# Dual-Port_Logging_Shield.net
KiCad netlist of a schematic drawn in EAGLE
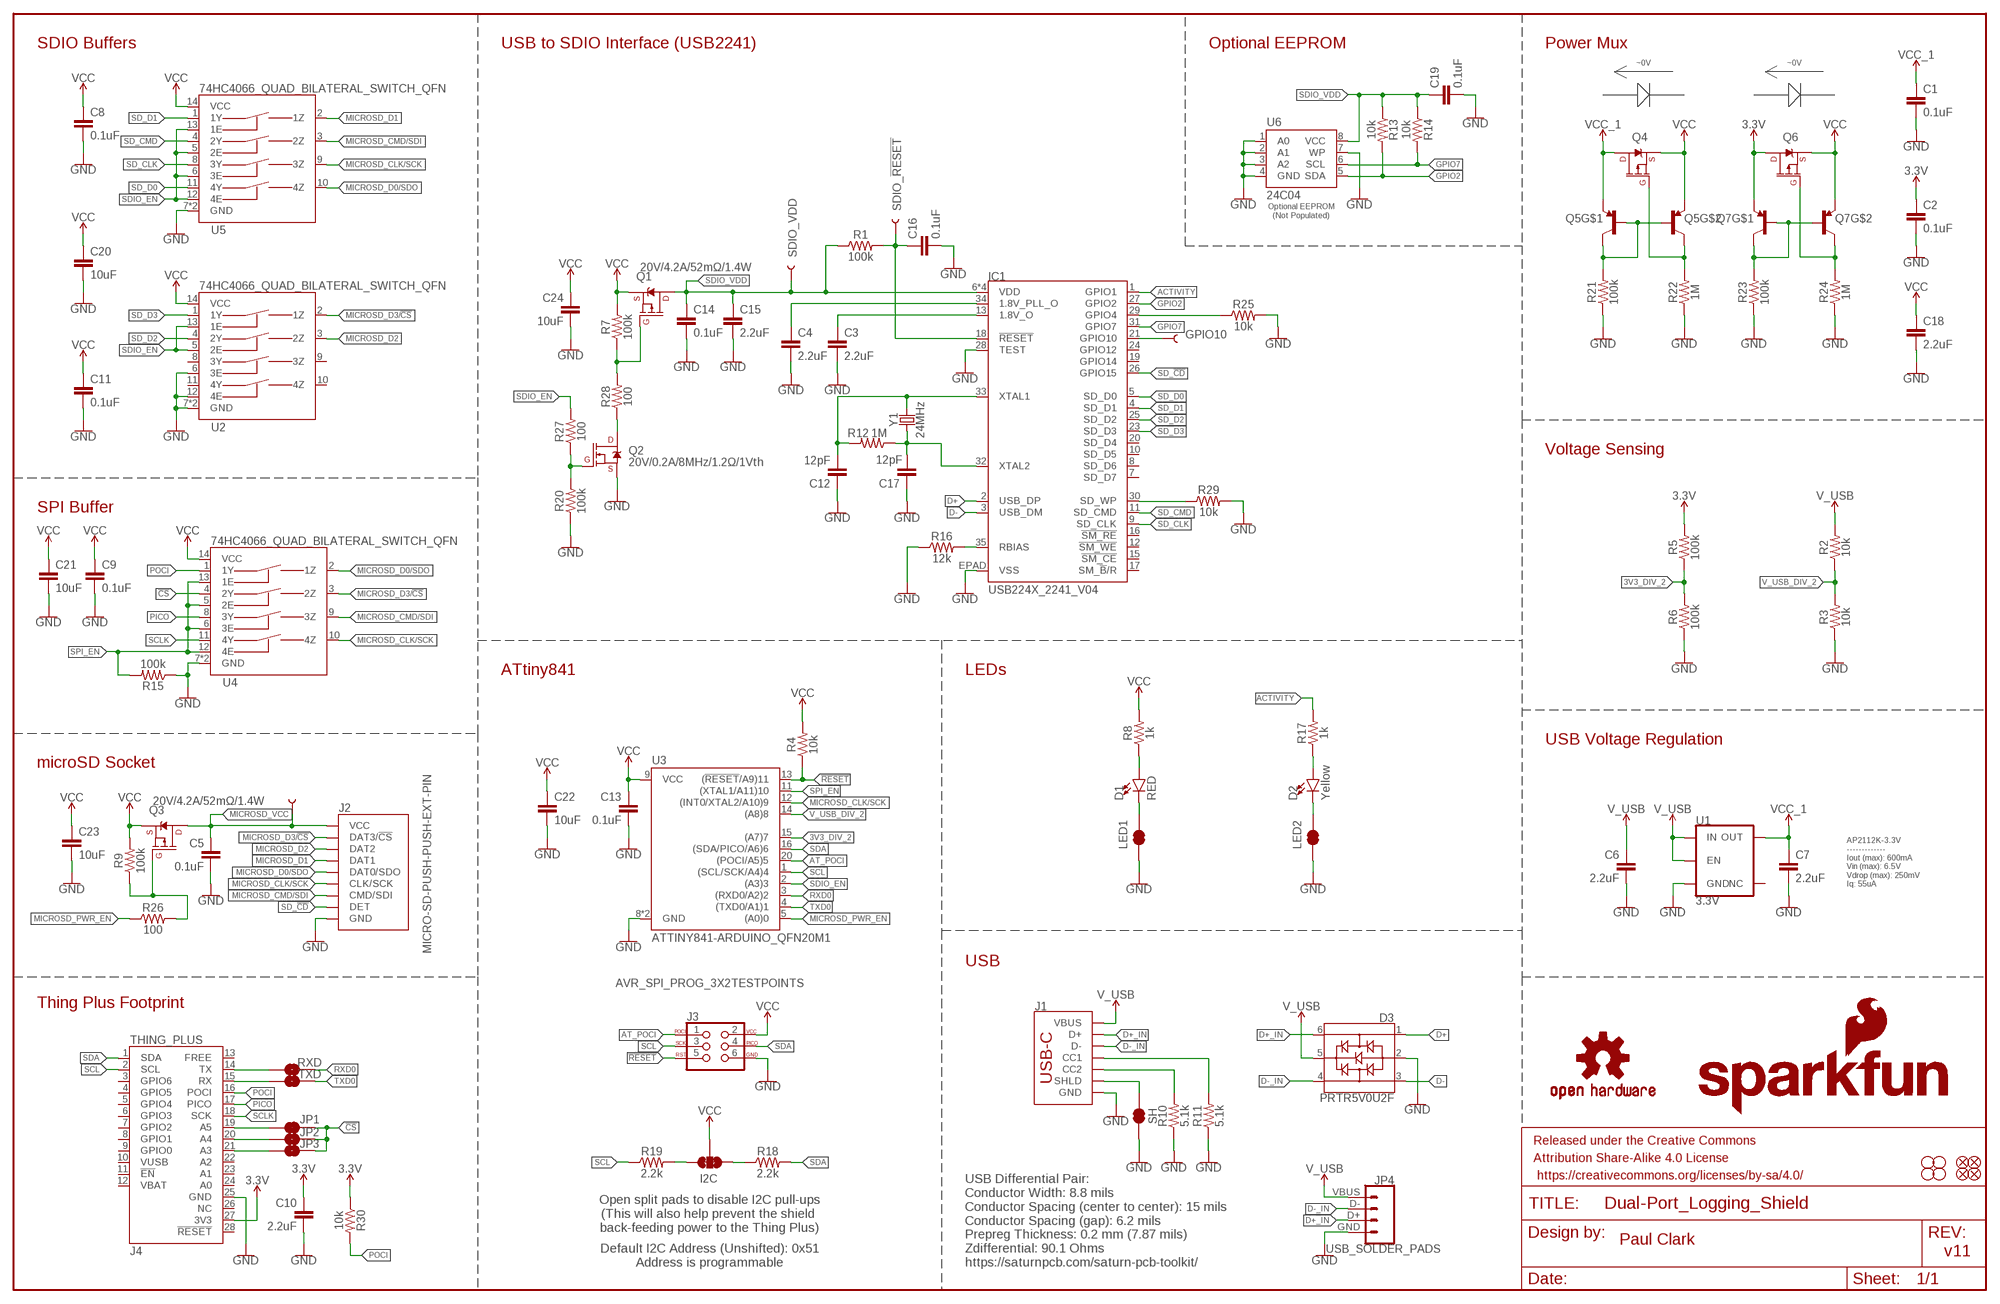
[diagram p0: schematic, sheet 1]

(export (version "E")
  (design (tool "Eeschema 10.0.6"))
  (components
    (comp (ref "C1")
      (value "0.1uF")
      (footprint "eagle-import:0402-TIGHT")
      (libsource (lib "eagle-import") (part "0.1UF-0402T-6.3V-10%-X7R"))
    )
    (comp (ref "C2")
      (value "0.1uF")
      (footprint "eagle-import:0402-TIGHT")
      (libsource (lib "eagle-import") (part "0.1UF-0402T-6.3V-10%-X7R"))
    )
    (comp (ref "C3")
      (value "2.2uF")
      (footprint "eagle-import:0402-TIGHT")
      (libsource (lib "eagle-import") (part "2.2UF-0402_TIGHT-10V-10%-X5R"))
    )
    (comp (ref "C4")
      (value "2.2uF")
      (footprint "eagle-import:0402-TIGHT")
      (libsource (lib "eagle-import") (part "2.2UF-0402_TIGHT-10V-10%-X5R"))
    )
    (comp (ref "C5")
      (value "0.1uF")
      (footprint "eagle-import:0402-TIGHT")
      (libsource (lib "eagle-import") (part "0.1UF-0402T-6.3V-10%-X7R"))
    )
    (comp (ref "C6")
      (value "2.2uF")
      (footprint "eagle-import:0402-TIGHT")
      (libsource (lib "eagle-import") (part "2.2UF-0402_TIGHT-10V-10%-X5R"))
    )
    (comp (ref "C7")
      (value "2.2uF")
      (footprint "eagle-import:0402-TIGHT")
      (libsource (lib "eagle-import") (part "2.2UF-0402_TIGHT-10V-10%-X5R"))
    )
    (comp (ref "C8")
      (value "0.1uF")
      (footprint "eagle-import:0402-TIGHT")
      (libsource (lib "eagle-import") (part "0.1UF-0402T-6.3V-10%-X7R"))
    )
    (comp (ref "C9")
      (value "0.1uF")
      (footprint "eagle-import:0402-TIGHT")
      (libsource (lib "eagle-import") (part "0.1UF-0402T-6.3V-10%-X7R"))
    )
    (comp (ref "C10")
      (value "2.2uF")
      (footprint "eagle-import:0402-TIGHT")
      (libsource (lib "eagle-import") (part "2.2UF-0402_TIGHT-10V-10%-X5R"))
    )
    (comp (ref "C11")
      (value "0.1uF")
      (footprint "eagle-import:0402-TIGHT")
      (libsource (lib "eagle-import") (part "0.1UF-0402T-6.3V-10%-X7R"))
    )
    (comp (ref "C12")
      (value "12pF")
      (footprint "eagle-import:0402-TIGHT")
      (libsource (lib "eagle-import") (part "12PF-0402T-50V-5%"))
    )
    (comp (ref "C13")
      (value "0.1uF")
      (footprint "eagle-import:0402-TIGHT")
      (libsource (lib "eagle-import") (part "0.1UF-0402T-6.3V-10%-X7R"))
    )
    (comp (ref "C14")
      (value "0.1uF")
      (footprint "eagle-import:0402-TIGHT")
      (libsource (lib "eagle-import") (part "0.1UF-0402T-6.3V-10%-X7R"))
    )
    (comp (ref "C15")
      (value "2.2uF")
      (footprint "eagle-import:0402-TIGHT")
      (libsource (lib "eagle-import") (part "2.2UF-0402_TIGHT-10V-10%-X5R"))
    )
    (comp (ref "C16")
      (value "0.1uF")
      (footprint "eagle-import:0402-TIGHT")
      (libsource (lib "eagle-import") (part "0.1UF-0402T-6.3V-10%-X7R"))
    )
    (comp (ref "C17")
      (value "12pF")
      (footprint "eagle-import:0402-TIGHT")
      (libsource (lib "eagle-import") (part "12PF-0402T-50V-5%"))
    )
    (comp (ref "C18")
      (value "2.2uF")
      (footprint "eagle-import:0402-TIGHT")
      (libsource (lib "eagle-import") (part "2.2UF-0402_TIGHT-10V-10%-X5R"))
    )
    (comp (ref "C19")
      (value "0.1uF")
      (footprint "eagle-import:0402-TIGHT")
      (libsource (lib "eagle-import") (part "0.1UF-0402T-6.3V-10%-X7R"))
    )
    (comp (ref "C20")
      (value "10uF")
      (footprint "eagle-import:0402-TIGHT")
      (libsource (lib "eagle-import") (part "10UF-0402T-6.3V-20%"))
    )
    (comp (ref "C21")
      (value "10uF")
      (footprint "eagle-import:0402-TIGHT")
      (libsource (lib "eagle-import") (part "10UF-0402T-6.3V-20%"))
    )
    (comp (ref "C22")
      (value "10uF")
      (footprint "eagle-import:0402-TIGHT")
      (libsource (lib "eagle-import") (part "10UF-0402T-6.3V-20%"))
    )
    (comp (ref "C23")
      (value "10uF")
      (footprint "eagle-import:0402-TIGHT")
      (libsource (lib "eagle-import") (part "10UF-0402T-6.3V-20%"))
    )
    (comp (ref "C24")
      (value "10uF")
      (footprint "eagle-import:0402-TIGHT")
      (libsource (lib "eagle-import") (part "10UF-0402T-6.3V-20%"))
    )
    (comp (ref "D1")
      (value "RED")
      (footprint "eagle-import:LED-0603")
      (libsource (lib "eagle-import") (part "LED-RED0603"))
    )
    (comp (ref "D2")
      (value "Yellow")
      (footprint "eagle-import:LED-0603")
      (libsource (lib "eagle-import") (part "LED-YELLOW0603"))
    )
    (comp (ref "D3")
      (value "PRTR5V0U2F")
      (footprint "eagle-import:SOT886")
      (libsource (lib "eagle-import") (part "PRTR5V0U2F"))
    )
    (comp (ref "FD1")
      (value "FIDUCIALUFIDUCIAL")
      (footprint "eagle-import:FIDUCIAL-MICRO")
      (libsource (lib "eagle-import") (part "FIDUCIALUFIDUCIAL"))
    )
    (comp (ref "FD2")
      (value "FIDUCIALUFIDUCIAL")
      (footprint "eagle-import:FIDUCIAL-MICRO")
      (libsource (lib "eagle-import") (part "FIDUCIALUFIDUCIAL"))
    )
    (comp (ref "FD3")
      (value "FIDUCIALUFIDUCIAL")
      (footprint "eagle-import:FIDUCIAL-MICRO")
      (libsource (lib "eagle-import") (part "FIDUCIALUFIDUCIAL"))
    )
    (comp (ref "FD4")
      (value "FIDUCIALUFIDUCIAL")
      (footprint "eagle-import:FIDUCIAL-MICRO")
      (libsource (lib "eagle-import") (part "FIDUCIALUFIDUCIAL"))
    )
    (comp (ref "FRAME1")
      (value "FRAME-LEDGER")
      (footprint "eagle-import:CREATIVE_COMMONS")
      (libsource (lib "eagle-import") (part "FRAME-LEDGER"))
    )
    (comp (ref "GPIO10")
      (value "TEST-POINT3")
      (footprint "eagle-import:PAD.03X.03")
      (libsource (lib "eagle-import") (part "TEST-POINT3"))
    )
    (comp (ref "H1")
      (value "STAND-OFF")
      (footprint "eagle-import:STAND-OFF")
      (libsource (lib "eagle-import") (part "STAND-OFF"))
    )
    (comp (ref "H2")
      (value "STAND-OFF")
      (footprint "eagle-import:STAND-OFF")
      (libsource (lib "eagle-import") (part "STAND-OFF"))
    )
    (comp (ref "H3")
      (value "STAND-OFF")
      (footprint "eagle-import:STAND-OFF")
      (libsource (lib "eagle-import") (part "STAND-OFF"))
    )
    (comp (ref "H4")
      (value "STAND-OFF")
      (footprint "eagle-import:STAND-OFF")
      (libsource (lib "eagle-import") (part "STAND-OFF"))
    )
    (comp (ref "I2C")
      (value "JUMPER-SMT_3_2-NC_TRACE_SILK")
      (footprint "eagle-import:SMT-JUMPER_3_2-NC_TRACE_SILK")
      (libsource (lib "eagle-import") (part "JUMPER-SMT_3_2-NC_TRACE_SILK"))
    )
    (comp (ref "IC1")
      (value "USB224X_2241_V04")
      (footprint "eagle-import:36-QFN")
      (libsource (lib "eagle-import") (part "USB224X_2241_V04"))
    )
    (comp (ref "J1")
      (value "USB_C_4-LAYER_PADS")
      (footprint "eagle-import:USB-C-16P_4LAYER-PADS")
      (libsource (lib "eagle-import") (part "USB_C_4-LAYER_PADS"))
    )
    (comp (ref "J2")
      (value "MICRO-SD-PUSH-PUSH-EXT-PIN")
      (footprint "eagle-import:MICROSD-EXTERNALPIN")
      (libsource (lib "eagle-import") (part "MICRO-SD-PUSH-PUSH-EXT-PIN"))
    )
    (comp (ref "J3")
      (value "AVR_SPI_PROG_3X2TESTPOINTS")
      (footprint "eagle-import:2X3_TEST_POINTS")
      (libsource (lib "eagle-import") (part "AVR_SPI_PROG_3X2TESTPOINTS"))
    )
    (comp (ref "J4")
      (value "THING_PLUS")
      (footprint "eagle-import:THING_PLUS")
      (libsource (lib "eagle-import") (part "THING_PLUS"))
    )
    (comp (ref "JP1")
      (value "JUMPER-SMT_2_NC_TRACE_SILK")
      (footprint "eagle-import:SMT-JUMPER_2_NC_TRACE_SILK")
      (libsource (lib "eagle-import") (part "JUMPER-SMT_2_NC_TRACE_SILK"))
    )
    (comp (ref "JP2")
      (value "JUMPER-SMT_2_NO_SILK")
      (footprint "eagle-import:SMT-JUMPER_2_NO_SILK")
      (libsource (lib "eagle-import") (part "JUMPER-SMT_2_NO_SILK"))
    )
    (comp (ref "JP3")
      (value "JUMPER-SMT_2_NO_SILK")
      (footprint "eagle-import:SMT-JUMPER_2_NO_SILK")
      (libsource (lib "eagle-import") (part "JUMPER-SMT_2_NO_SILK"))
    )
    (comp (ref "JP4")
      (value "USB_SOLDER_PADS")
      (footprint "eagle-import:USB-SOLDER-PADS")
      (libsource (lib "eagle-import") (part "USB_SOLDER_PADS"))
    )
    (comp (ref "LED1")
      (value "JUMPER-SMT_2_NC_TRACE_SILK")
      (footprint "eagle-import:SMT-JUMPER_2_NC_TRACE_SILK")
      (libsource (lib "eagle-import") (part "JUMPER-SMT_2_NC_TRACE_SILK"))
    )
    (comp (ref "LED2")
      (value "JUMPER-SMT_2_NC_TRACE_SILK")
      (footprint "eagle-import:SMT-JUMPER_2_NC_TRACE_SILK")
      (libsource (lib "eagle-import") (part "JUMPER-SMT_2_NC_TRACE_SILK"))
    )
    (comp (ref "LOGO2")
      (value "OSHW-LOGOMINI")
      (footprint "eagle-import:OSHW-LOGO-MINI")
      (libsource (lib "eagle-import") (part "OSHW-LOGOMINI"))
    )
    (comp (ref "LOGO3")
      (value "OSHW-LOGOMINI")
      (footprint "eagle-import:OSHW-LOGO-MINI")
      (libsource (lib "eagle-import") (part "OSHW-LOGOMINI"))
    )
    (comp (ref "LOGO4")
      (value "SFE_LOGO_FLAME.2_INCH")
      (footprint "eagle-import:SFE_LOGO_FLAME_.2")
      (libsource (lib "eagle-import") (part "SFE_LOGO_FLAME.2_INCH"))
    )
    (comp (ref "LOGO5")
      (value "SFE_LOGO_NAME_FLAME.1_INCH")
      (footprint "eagle-import:SFE_LOGO_NAME_FLAME_.1")
      (libsource (lib "eagle-import") (part "SFE_LOGO_NAME_FLAME.1_INCH"))
    )
    (comp (ref "MICROSD_VCC")
      (value "TEST-POINT3")
      (footprint "eagle-import:PAD.03X.03")
      (libsource (lib "eagle-import") (part "TEST-POINT3"))
    )
    (comp (ref "Q1")
      (value "20V/4.2A/52mΩ/1.4W")
      (footprint "eagle-import:SOT23-3")
      (libsource (lib "eagle-import") (part "MOSFET_PCH-DMG2305UX-7"))
    )
    (comp (ref "Q2")
      (value "20V/0.2A/8MHz/1.2Ω/1Vth")
      (footprint "eagle-import:SOT-416FL")
      (libsource (lib "eagle-import") (part "MOSFET-NCH-RE1C002UNTCL"))
    )
    (comp (ref "Q3")
      (value "20V/4.2A/52mΩ/1.4W")
      (footprint "eagle-import:SOT23-3")
      (libsource (lib "eagle-import") (part "MOSFET_PCH-DMG2305UX-7"))
    )
    (comp (ref "Q4")
      (value "20V/4.2A/52mΩ/1.4W")
      (footprint "eagle-import:SOT23-3")
      (libsource (lib "eagle-import") (part "MOSFET_PCH-DMG2305UX-7"))
    )
    (comp (ref "Q5")
      (value "TRANS_PNP_DUALSOT-363")
      (footprint "eagle-import:SOT363_PHILIPS")
      (libsource (lib "eagle-import") (part "TRANS_PNP_DUALSOT-363"))
    )
    (comp (ref "Q6")
      (value "20V/4.2A/52mΩ/1.4W")
      (footprint "eagle-import:SOT23-3")
      (libsource (lib "eagle-import") (part "MOSFET_PCH-DMG2305UX-7"))
    )
    (comp (ref "Q7")
      (value "TRANS_PNP_DUALSOT-363")
      (footprint "eagle-import:SOT363_PHILIPS")
      (libsource (lib "eagle-import") (part "TRANS_PNP_DUALSOT-363"))
    )
    (comp (ref "R1")
      (value "100k")
      (footprint "eagle-import:0402-TIGHT")
      (libsource (lib "eagle-import") (part "100KOHM-0402T-1/16W-1%"))
    )
    (comp (ref "R2")
      (value "10k")
      (footprint "eagle-import:0402-TIGHT")
      (libsource (lib "eagle-import") (part "10KOHM-0402T-1/16W-1%"))
    )
    (comp (ref "R3")
      (value "10k")
      (footprint "eagle-import:0402-TIGHT")
      (libsource (lib "eagle-import") (part "10KOHM-0402T-1/16W-1%"))
    )
    (comp (ref "R4")
      (value "10k")
      (footprint "eagle-import:0402-TIGHT")
      (libsource (lib "eagle-import") (part "10KOHM-0402T-1/16W-1%"))
    )
    (comp (ref "R5")
      (value "100k")
      (footprint "eagle-import:0402-TIGHT")
      (libsource (lib "eagle-import") (part "100KOHM-0402T-1/16W-1%"))
    )
    (comp (ref "R6")
      (value "100k")
      (footprint "eagle-import:0402-TIGHT")
      (libsource (lib "eagle-import") (part "100KOHM-0402T-1/16W-1%"))
    )
    (comp (ref "R7")
      (value "100k")
      (footprint "eagle-import:0402-TIGHT")
      (libsource (lib "eagle-import") (part "100KOHM-0402T-1/16W-1%"))
    )
    (comp (ref "R8")
      (value "1k")
      (footprint "eagle-import:0402-TIGHT")
      (libsource (lib "eagle-import") (part "1KOHM-0402T-1/16W-1%"))
    )
    (comp (ref "R9")
      (value "100k")
      (footprint "eagle-import:0402-TIGHT")
      (libsource (lib "eagle-import") (part "100KOHM-0402T-1/16W-1%"))
    )
    (comp (ref "R10")
      (value "5.1k")
      (footprint "eagle-import:0402-TIGHT")
      (libsource (lib "eagle-import") (part "5.1KOHM-0402T-1/16W-1%"))
    )
    (comp (ref "R11")
      (value "5.1k")
      (footprint "eagle-import:0402-TIGHT")
      (libsource (lib "eagle-import") (part "5.1KOHM-0402T-1/16W-1%"))
    )
    (comp (ref "R12")
      (value "1M")
      (footprint "eagle-import:0402-TIGHT")
      (libsource (lib "eagle-import") (part "1MOHM-0402T-1/16W-5%"))
    )
    (comp (ref "R13")
      (value "10k")
      (footprint "eagle-import:0402-TIGHT")
      (libsource (lib "eagle-import") (part "10KOHM-0402T-1/16W-1%"))
    )
    (comp (ref "R14")
      (value "10k")
      (footprint "eagle-import:0402-TIGHT")
      (libsource (lib "eagle-import") (part "10KOHM-0402T-1/16W-1%"))
    )
    (comp (ref "R15")
      (value "100k")
      (footprint "eagle-import:0402-TIGHT")
      (libsource (lib "eagle-import") (part "100KOHM-0402T-1/16W-1%"))
    )
    (comp (ref "R16")
      (value "12k")
      (footprint "eagle-import:0603")
      (libsource (lib "eagle-import") (part "12KOHM-0603-1/10W-1%"))
    )
    (comp (ref "R17")
      (value "1k")
      (footprint "eagle-import:0402-TIGHT")
      (libsource (lib "eagle-import") (part "1KOHM-0402T-1/16W-1%"))
    )
    (comp (ref "R18")
      (value "2.2k")
      (footprint "eagle-import:0402-TIGHT")
      (libsource (lib "eagle-import") (part "2.2KOHM-0402T-1/16W-1%"))
    )
    (comp (ref "R19")
      (value "2.2k")
      (footprint "eagle-import:0402-TIGHT")
      (libsource (lib "eagle-import") (part "2.2KOHM-0402T-1/16W-1%"))
    )
    (comp (ref "R20")
      (value "100k")
      (footprint "eagle-import:0402-TIGHT")
      (libsource (lib "eagle-import") (part "100KOHM-0402T-1/16W-1%"))
    )
    (comp (ref "R21")
      (value "100k")
      (footprint "eagle-import:0402-TIGHT")
      (libsource (lib "eagle-import") (part "100KOHM-0402T-1/16W-1%"))
    )
    (comp (ref "R22")
      (value "1M")
      (footprint "eagle-import:0402-TIGHT")
      (libsource (lib "eagle-import") (part "1MOHM-0402T-1/16W-5%"))
    )
    (comp (ref "R23")
      (value "100k")
      (footprint "eagle-import:0402-TIGHT")
      (libsource (lib "eagle-import") (part "100KOHM-0402T-1/16W-1%"))
    )
    (comp (ref "R24")
      (value "1M")
      (footprint "eagle-import:0402-TIGHT")
      (libsource (lib "eagle-import") (part "1MOHM-0402T-1/16W-5%"))
    )
    (comp (ref "R25")
      (value "10k")
      (footprint "eagle-import:0402-TIGHT")
      (libsource (lib "eagle-import") (part "10KOHM-0402T-1/16W-1%"))
    )
    (comp (ref "R26")
      (value "100")
      (footprint "eagle-import:0402-TIGHT")
      (libsource (lib "eagle-import") (part "100OHM-0402-TIGHT-1/16W-1%"))
    )
    (comp (ref "R27")
      (value "100")
      (footprint "eagle-import:0402-TIGHT")
      (libsource (lib "eagle-import") (part "100OHM-0402-TIGHT-1/16W-1%"))
    )
    (comp (ref "R28")
      (value "100")
      (footprint "eagle-import:0402-TIGHT")
      (libsource (lib "eagle-import") (part "100OHM-0402-TIGHT-1/16W-1%"))
    )
    (comp (ref "R29")
      (value "10k")
      (footprint "eagle-import:0402-TIGHT")
      (libsource (lib "eagle-import") (part "10KOHM-0402T-1/16W-1%"))
    )
    (comp (ref "R30")
      (value "10k")
      (footprint "eagle-import:0402-TIGHT")
      (libsource (lib "eagle-import") (part "10KOHM-0402T-1/16W-1%"))
    )
    (comp (ref "RXD")
      (value "JUMPER-SMT_2_NO_SILK")
      (footprint "eagle-import:SMT-JUMPER_2_NO_SILK")
      (libsource (lib "eagle-import") (part "JUMPER-SMT_2_NO_SILK"))
    )
    (comp (ref "SDIO_!RESET!")
      (value "TEST-POINT3")
      (footprint "eagle-import:PAD.03X.03")
      (libsource (lib "eagle-import") (part "TEST-POINT3"))
    )
    (comp (ref "SDIO_VDD")
      (value "TEST-POINT3")
      (footprint "eagle-import:PAD.03X.03")
      (libsource (lib "eagle-import") (part "TEST-POINT3"))
    )
    (comp (ref "SH")
      (value "JUMPER-SMT_2_NC_TRACE_NO-SILK")
      (footprint "eagle-import:SMT-JUMPER_2_NC_TRACE_NO-SILK")
      (libsource (lib "eagle-import") (part "JUMPER-SMT_2_NC_TRACE_NO-SILK"))
    )
    (comp (ref "TXD")
      (value "JUMPER-SMT_2_NO_SILK")
      (footprint "eagle-import:SMT-JUMPER_2_NO_SILK")
      (libsource (lib "eagle-import") (part "JUMPER-SMT_2_NO_SILK"))
    )
    (comp (ref "U1")
      (value "3.3V")
      (footprint "eagle-import:SOT23-5")
      (libsource (lib "eagle-import") (part "V_REG_AP2112K-3.3V"))
    )
    (comp (ref "U2")
      (value "74HC4066_QUAD_BILATERAL_SWITCH_QFN")
      (footprint "eagle-import:14-QFN")
      (libsource (lib "eagle-import") (part "74HC4066_QUAD_BILATERAL_SWITCH_QFN"))
    )
    (comp (ref "U3")
      (value "ATTINY841-ARDUINO_QFN20M1")
      (footprint "eagle-import:QFN20_20M1")
      (fields (field (name "DIGIKEY_PART") "ATTINY841-MU-ND"))
      (libsource (lib "eagle-import") (part "ATTINY841-ARDUINO_QFN20M1"))
    )
    (comp (ref "U4")
      (value "74HC4066_QUAD_BILATERAL_SWITCH_QFN")
      (footprint "eagle-import:14-QFN")
      (libsource (lib "eagle-import") (part "74HC4066_QUAD_BILATERAL_SWITCH_QFN"))
    )
    (comp (ref "U5")
      (value "74HC4066_QUAD_BILATERAL_SWITCH_QFN")
      (footprint "eagle-import:14-QFN")
      (libsource (lib "eagle-import") (part "74HC4066_QUAD_BILATERAL_SWITCH_QFN"))
    )
    (comp (ref "U6")
      (value "24C04")
      (footprint "eagle-import:SO08")
      (libsource (lib "eagle-import") (part "EEPROM-I2C256K"))
    )
    (comp (ref "Y1")
      (value "24MHz")
      (footprint "eagle-import:CRYSTAL-SMD-2.0X1.6MM")
      (libsource (lib "eagle-import") (part "CRYSTAL-24MHZ-SMD-2.0X1.6MM"))
    )
  )
  (nets
    (net (code "1") (name "/MICROSD_D3{slash}~{CS}") (class "Default")
      (node (ref "J2") (pin "2") (pinfunction "DAT3/~{CS}_2") (pintype "bidirectional"))
      (node (ref "U2") (pin "2") (pinfunction "1Z_2") (pintype "bidirectional"))
      (node (ref "U4") (pin "3") (pinfunction "2Z_3") (pintype "bidirectional"))
    )
    (net (code "2") (name "/SD_~{CD}") (class "Default")
      (node (ref "IC1") (pin "26") (pinfunction "GPIO15_26") (pintype "bidirectional"))
      (node (ref "J2") (pin "9") (pinfunction "DET_9") (pintype "bidirectional"))
    )
    (net (code "3") (name "/~{CS}") (class "Default")
      (node (ref "JP1") (pin "2") (pinfunction "2_2") (pintype "passive"))
      (node (ref "JP2") (pin "2") (pinfunction "2_2") (pintype "passive"))
      (node (ref "JP3") (pin "2") (pinfunction "2_2") (pintype "passive"))
      (node (ref "U4") (pin "4") (pinfunction "2Y_4") (pintype "bidirectional"))
    )
    (net (code "4") (name "/~{RESET}") (class "Default")
      (node (ref "J3") (pin "5") (pinfunction "5_5") (pintype "passive"))
      (node (ref "R4") (pin "1") (pinfunction "1_1") (pintype "passive"))
      (node (ref "U3") (pin "13") (pinfunction "(~{RESET}/A9)11_13") (pintype "bidirectional"))
    )
    (net (code "5") (name "3.3V") (class "Default")
      (node (ref "C10") (pin "1") (pinfunction "1_1") (pintype "passive"))
      (node (ref "C2") (pin "1") (pinfunction "1_1") (pintype "passive"))
      (node (ref "J4") (pin "27") (pinfunction "3V3_27") (pintype "bidirectional"))
      (node (ref "Q6") (pin "3") (pinfunction "D_3") (pintype "bidirectional"))
      (node (ref "Q7") (pin "1") (pinfunction "E_1") (pintype "passive"))
      (node (ref "R30") (pin "1") (pinfunction "1_1") (pintype "passive"))
      (node (ref "R5") (pin "2") (pinfunction "2_2") (pintype "passive"))
    )
    (net (code "6") (name "3V3_DIV_2") (class "Default")
      (node (ref "R5") (pin "1") (pinfunction "1_1") (pintype "passive"))
      (node (ref "R6") (pin "2") (pinfunction "2_2") (pintype "passive"))
      (node (ref "U3") (pin "15") (pinfunction "(A7)7_15") (pintype "bidirectional"))
    )
    (net (code "7") (name "ACTIVITY") (class "Default")
      (node (ref "IC1") (pin "1") (pinfunction "GPIO1_1") (pintype "bidirectional"))
      (node (ref "R17") (pin "2") (pinfunction "2_2") (pintype "passive"))
    )
    (net (code "8") (name "AT_POCI") (class "Default")
      (node (ref "J3") (pin "1") (pinfunction "1_1") (pintype "passive"))
      (node (ref "U3") (pin "20") (pinfunction "(POCI/A5)5_20") (pintype "bidirectional"))
    )
    (net (code "9") (name "D+") (class "Default")
      (node (ref "D3") (pin "1") (pinfunction "1_1") (pintype "bidirectional"))
      (node (ref "IC1") (pin "2") (pinfunction "USB_DP_2") (pintype "bidirectional"))
    )
    (net (code "10") (name "D+_IN") (class "Default")
      (node (ref "D3") (pin "6") (pinfunction "6_6") (pintype "bidirectional"))
      (node (ref "J1") (pin "A6") (pinfunction "D+_A6") (pintype "bidirectional"))
      (node (ref "J1") (pin "B6") (pinfunction "D+_B6") (pintype "bidirectional"))
      (node (ref "JP4") (pin "D+") (pinfunction "3_D+") (pintype "passive"))
    )
    (net (code "11") (name "D-") (class "Default")
      (node (ref "D3") (pin "3") (pinfunction "3_3") (pintype "bidirectional"))
      (node (ref "IC1") (pin "3") (pinfunction "USB_DM_3") (pintype "bidirectional"))
    )
    (net (code "12") (name "D-_IN") (class "Default")
      (node (ref "D3") (pin "4") (pinfunction "4_4") (pintype "bidirectional"))
      (node (ref "J1") (pin "A7") (pinfunction "D-_A7") (pintype "bidirectional"))
      (node (ref "J1") (pin "B7") (pinfunction "D-_B7") (pintype "bidirectional"))
      (node (ref "JP4") (pin "D-") (pinfunction "2_D-") (pintype "passive"))
    )
    (net (code "13") (name "GND") (class "Default")
      (node (ref "C1") (pin "2") (pinfunction "2_2") (pintype "passive"))
      (node (ref "C10") (pin "2") (pinfunction "2_2") (pintype "passive"))
      (node (ref "C11") (pin "2") (pinfunction "2_2") (pintype "passive"))
      (node (ref "C12") (pin "1") (pinfunction "1_1") (pintype "passive"))
      (node (ref "C13") (pin "2") (pinfunction "2_2") (pintype "passive"))
      (node (ref "C14") (pin "2") (pinfunction "2_2") (pintype "passive"))
      (node (ref "C15") (pin "2") (pinfunction "2_2") (pintype "passive"))
      (node (ref "C16") (pin "2") (pinfunction "2_2") (pintype "passive"))
      (node (ref "C17") (pin "1") (pinfunction "1_1") (pintype "passive"))
      (node (ref "C18") (pin "2") (pinfunction "2_2") (pintype "passive"))
      (node (ref "C19") (pin "2") (pinfunction "2_2") (pintype "passive"))
      (node (ref "C2") (pin "2") (pinfunction "2_2") (pintype "passive"))
      (node (ref "C20") (pin "2") (pinfunction "2_2") (pintype "passive"))
      (node (ref "C21") (pin "2") (pinfunction "2_2") (pintype "passive"))
      (node (ref "C22") (pin "2") (pinfunction "2_2") (pintype "passive"))
      (node (ref "C23") (pin "2") (pinfunction "2_2") (pintype "passive"))
      (node (ref "C24") (pin "2") (pinfunction "2_2") (pintype "passive"))
      (node (ref "C3") (pin "2") (pinfunction "2_2") (pintype "passive"))
      (node (ref "C4") (pin "2") (pinfunction "2_2") (pintype "passive"))
      (node (ref "C5") (pin "2") (pinfunction "2_2") (pintype "passive"))
      (node (ref "C6") (pin "2") (pinfunction "2_2") (pintype "passive"))
      (node (ref "C7") (pin "2") (pinfunction "2_2") (pintype "passive"))
      (node (ref "C8") (pin "2") (pinfunction "2_2") (pintype "passive"))
      (node (ref "C9") (pin "2") (pinfunction "2_2") (pintype "passive"))
      (node (ref "D3") (pin "2") (pinfunction "2_2") (pintype "power_in"))
      (node (ref "IC1") (pin "28") (pinfunction "TEST_28") (pintype "bidirectional"))
      (node (ref "IC1") (pin "EPAD") (pinfunction "VSS_EPAD") (pintype "power_in"))
      (node (ref "J1") (pin "GND") (pinfunction "GND_GND") (pintype "bidirectional"))
      (node (ref "J1") (pin "GND2") (pinfunction "GND_GND2") (pintype "bidirectional"))
      (node (ref "J2") (pin "10") (pinfunction "GND_10") (pintype "bidirectional"))
      (node (ref "J2") (pin "11") (pinfunction "GND_11") (pintype "bidirectional"))
      (node (ref "J2") (pin "12") (pinfunction "GND_12") (pintype "bidirectional"))
      (node (ref "J2") (pin "13") (pinfunction "GND_13") (pintype "bidirectional"))
      (node (ref "J2") (pin "6") (pinfunction "GND_6") (pintype "bidirectional"))
      (node (ref "J3") (pin "6") (pinfunction "6_6") (pintype "passive"))
      (node (ref "J4") (pin "25") (pinfunction "GND_25") (pintype "bidirectional"))
      (node (ref "JP4") (pin "GND") (pinfunction "4_GND") (pintype "passive"))
      (node (ref "LED1") (pin "1") (pinfunction "1_1") (pintype "passive"))
      (node (ref "LED2") (pin "1") (pinfunction "1_1") (pintype "passive"))
      (node (ref "Q2") (pin "2") (pinfunction "S_2") (pintype "bidirectional"))
      (node (ref "R10") (pin "1") (pinfunction "1_1") (pintype "passive"))
      (node (ref "R11") (pin "1") (pinfunction "1_1") (pintype "passive"))
      (node (ref "R15") (pin "1") (pinfunction "1_1") (pintype "passive"))
      (node (ref "R16") (pin "1") (pinfunction "1_1") (pintype "passive"))
      (node (ref "R20") (pin "1") (pinfunction "1_1") (pintype "passive"))
      (node (ref "R21") (pin "1") (pinfunction "1_1") (pintype "passive"))
      (node (ref "R22") (pin "1") (pinfunction "1_1") (pintype "passive"))
      (node (ref "R23") (pin "1") (pinfunction "1_1") (pintype "passive"))
      (node (ref "R24") (pin "1") (pinfunction "1_1") (pintype "passive"))
      (node (ref "R25") (pin "2") (pinfunction "2_2") (pintype "passive"))
      (node (ref "R29") (pin "2") (pinfunction "2_2") (pintype "passive"))
      (node (ref "R3") (pin "1") (pinfunction "1_1") (pintype "passive"))
      (node (ref "R6") (pin "1") (pinfunction "1_1") (pintype "passive"))
      (node (ref "SH") (pin "2") (pinfunction "2_2") (pintype "passive"))
      (node (ref "U1") (pin "2") (pinfunction "GND_2") (pintype "input"))
      (node (ref "U2") (pin "12") (pinfunction "4E_12") (pintype "bidirectional"))
      (node (ref "U2") (pin "6") (pinfunction "3E_6") (pintype "bidirectional"))
      (node (ref "U2") (pin "7") (pinfunction "GND_7") (pintype "bidirectional"))
      (node (ref "U2") (pin "EPAD") (pinfunction "GND_EPAD") (pintype "bidirectional"))
      (node (ref "U3") (pin "8") (pinfunction "GND_8") (pintype "power_in"))
      (node (ref "U3") (pin "PAD") (pinfunction "GND_PAD") (pintype "power_in"))
      (node (ref "U4") (pin "7") (pinfunction "GND_7") (pintype "bidirectional"))
      (node (ref "U4") (pin "EPAD") (pinfunction "GND_EPAD") (pintype "bidirectional"))
      (node (ref "U5") (pin "7") (pinfunction "GND_7") (pintype "bidirectional"))
      (node (ref "U5") (pin "EPAD") (pinfunction "GND_EPAD") (pintype "bidirectional"))
      (node (ref "U6") (pin "1") (pinfunction "A0_1") (pintype "bidirectional"))
      (node (ref "U6") (pin "2") (pinfunction "A1_2") (pintype "bidirectional"))
      (node (ref "U6") (pin "3") (pinfunction "A2_3") (pintype "bidirectional"))
      (node (ref "U6") (pin "4") (pinfunction "GND_4") (pintype "power_in"))
      (node (ref "U6") (pin "7") (pinfunction "WP_7") (pintype "bidirectional"))
    )
    (net (code "14") (name "GPIO2") (class "Default")
      (node (ref "IC1") (pin "27") (pinfunction "GPIO2_27") (pintype "bidirectional"))
      (node (ref "R13") (pin "2") (pinfunction "2_2") (pintype "passive"))
      (node (ref "U6") (pin "5") (pinfunction "SDA_5") (pintype "bidirectional"))
    )
    (net (code "15") (name "GPIO7") (class "Default")
      (node (ref "IC1") (pin "31") (pinfunction "GPIO7_31") (pintype "bidirectional"))
      (node (ref "R14") (pin "2") (pinfunction "2_2") (pintype "passive"))
      (node (ref "U6") (pin "6") (pinfunction "SCL_6") (pintype "bidirectional"))
    )
    (net (code "16") (name "MICROSD_CLK{slash}SCK") (class "Default")
      (node (ref "J2") (pin "5") (pinfunction "CLK/SCK_5") (pintype "bidirectional"))
      (node (ref "U3") (pin "12") (pinfunction "(INT0/XTAL2/A10)9_12") (pintype "bidirectional"))
      (node (ref "U4") (pin "10") (pinfunction "4Z_10") (pintype "bidirectional"))
      (node (ref "U5") (pin "9") (pinfunction "3Z_9") (pintype "bidirectional"))
    )
    (net (code "17") (name "MICROSD_CMD{slash}SDI") (class "Default")
      (node (ref "J2") (pin "3") (pinfunction "CMD/SDI_3") (pintype "bidirectional"))
      (node (ref "U4") (pin "9") (pinfunction "3Z_9") (pintype "bidirectional"))
      (node (ref "U5") (pin "3") (pinfunction "2Z_3") (pintype "bidirectional"))
    )
    (net (code "18") (name "MICROSD_D0{slash}SDO") (class "Default")
      (node (ref "J2") (pin "7") (pinfunction "DAT0/SDO_7") (pintype "bidirectional"))
      (node (ref "U4") (pin "2") (pinfunction "1Z_2") (pintype "bidirectional"))
      (node (ref "U5") (pin "10") (pinfunction "4Z_10") (pintype "bidirectional"))
    )
    (net (code "19") (name "MICROSD_D1") (class "Default")
      (node (ref "J2") (pin "8") (pinfunction "DAT1_8") (pintype "bidirectional"))
      (node (ref "U5") (pin "2") (pinfunction "1Z_2") (pintype "bidirectional"))
    )
    (net (code "20") (name "MICROSD_D2") (class "Default")
      (node (ref "J2") (pin "1") (pinfunction "DAT2_1") (pintype "bidirectional"))
      (node (ref "U2") (pin "3") (pinfunction "2Z_3") (pintype "bidirectional"))
    )
    (net (code "21") (name "MICROSD_PWR_EN") (class "Default")
      (node (ref "R26") (pin "1") (pinfunction "1_1") (pintype "passive"))
      (node (ref "U3") (pin "5") (pinfunction "(A0)0_5") (pintype "bidirectional"))
    )
    (net (code "22") (name "MICROSD_VCC") (class "Default")
      (node (ref "C5") (pin "1") (pinfunction "1_1") (pintype "passive"))
      (node (ref "J2") (pin "4") (pinfunction "VCC_4") (pintype "bidirectional"))
      (node (ref "MICROSD_VCC") (pin "1") (pinfunction "1_1") (pintype "bidirectional"))
      (node (ref "Q3") (pin "3") (pinfunction "D_3") (pintype "bidirectional"))
    )
    (net (code "23") (name "Net-(D1-PadA)") (class "Default")
      (node (ref "D1") (pin "A") (pinfunction "A_A") (pintype "passive"))
      (node (ref "R8") (pin "1") (pinfunction "1_1") (pintype "passive"))
    )
    (net (code "24") (name "Net-(D1-PadC)") (class "Default")
      (node (ref "D1") (pin "C") (pinfunction "C_C") (pintype "passive"))
      (node (ref "LED1") (pin "2") (pinfunction "2_2") (pintype "passive"))
    )
    (net (code "25") (name "Net-(D2-PadA)") (class "Default")
      (node (ref "D2") (pin "A") (pinfunction "A_A") (pintype "passive"))
      (node (ref "R17") (pin "1") (pinfunction "1_1") (pintype "passive"))
    )
    (net (code "26") (name "Net-(D2-PadC)") (class "Default")
      (node (ref "D2") (pin "C") (pinfunction "C_C") (pintype "passive"))
      (node (ref "LED2") (pin "2") (pinfunction "2_2") (pintype "passive"))
    )
    (net (code "27") (name "Net-(I2C-Pad1)") (class "Default")
      (node (ref "I2C") (pin "1") (pinfunction "1_1") (pintype "passive"))
      (node (ref "R18") (pin "1") (pinfunction "1_1") (pintype "passive"))
    )
    (net (code "28") (name "Net-(I2C-Pad3)") (class "Default")
      (node (ref "I2C") (pin "3") (pinfunction "3_3") (pintype "passive"))
      (node (ref "R19") (pin "2") (pinfunction "2_2") (pintype "passive"))
    )
    (net (code "29") (name "Net-(IC1-1.8V_O)") (class "Default")
      (node (ref "C3") (pin "1") (pinfunction "1_1") (pintype "passive"))
      (node (ref "IC1") (pin "13") (pinfunction "1.8V_O_13") (pintype "output"))
    )
    (net (code "30") (name "Net-(IC1-1.8V_PLL_O)") (class "Default")
      (node (ref "C4") (pin "1") (pinfunction "1_1") (pintype "passive"))
      (node (ref "IC1") (pin "34") (pinfunction "1.8V_PLL_O_34") (pintype "output"))
    )
    (net (code "31") (name "Net-(IC1-GPIO4)") (class "Default")
      (node (ref "IC1") (pin "29") (pinfunction "GPIO4_29") (pintype "bidirectional"))
      (node (ref "R25") (pin "1") (pinfunction "1_1") (pintype "passive"))
    )
    (net (code "32") (name "Net-(IC1-GPIO10)") (class "Default")
      (node (ref "GPIO10") (pin "1") (pinfunction "1_1") (pintype "bidirectional"))
      (node (ref "IC1") (pin "21") (pinfunction "GPIO10_21") (pintype "bidirectional"))
    )
    (net (code "33") (name "Net-(IC1-RBIAS)") (class "Default")
      (node (ref "IC1") (pin "35") (pinfunction "RBIAS_35") (pintype "bidirectional"))
      (node (ref "R16") (pin "2") (pinfunction "2_2") (pintype "passive"))
    )
    (net (code "34") (name "Net-(IC1-SD_WP)") (class "Default")
      (node (ref "IC1") (pin "30") (pinfunction "SD_WP_30") (pintype "bidirectional"))
      (node (ref "R29") (pin "1") (pinfunction "1_1") (pintype "passive"))
    )
    (net (code "35") (name "Net-(IC1-XTAL1)") (class "Default")
      (node (ref "C12") (pin "2") (pinfunction "2_2") (pintype "passive"))
      (node (ref "IC1") (pin "33") (pinfunction "XTAL1_33") (pintype "bidirectional"))
      (node (ref "R12") (pin "2") (pinfunction "2_2") (pintype "passive"))
      (node (ref "Y1") (pin "3") (pinfunction "2_3") (pintype "passive"))
    )
    (net (code "36") (name "Net-(IC1-XTAL2)") (class "Default")
      (node (ref "C17") (pin "2") (pinfunction "2_2") (pintype "passive"))
      (node (ref "IC1") (pin "32") (pinfunction "XTAL2_32") (pintype "bidirectional"))
      (node (ref "R12") (pin "1") (pinfunction "1_1") (pintype "passive"))
      (node (ref "Y1") (pin "1") (pinfunction "1_1") (pintype "passive"))
    )
    (net (code "37") (name "Net-(IC1-~{RESET})") (class "Default")
      (node (ref "C16") (pin "1") (pinfunction "1_1") (pintype "passive"))
      (node (ref "IC1") (pin "18") (pinfunction "~{RESET}_18") (pintype "input"))
      (node (ref "R1") (pin "2") (pinfunction "2_2") (pintype "passive"))
      (node (ref "SDIO_!RESET!") (pin "1") (pinfunction "1_1") (pintype "bidirectional"))
    )
    (net (code "38") (name "Net-(J1-CC1)") (class "Default")
      (node (ref "J1") (pin "A5") (pinfunction "CC1_A5") (pintype "bidirectional"))
      (node (ref "R11") (pin "2") (pinfunction "2_2") (pintype "passive"))
    )
    (net (code "39") (name "Net-(J1-CC2)") (class "Default")
      (node (ref "J1") (pin "B5") (pinfunction "CC2_B5") (pintype "bidirectional"))
      (node (ref "R10") (pin "2") (pinfunction "2_2") (pintype "passive"))
    )
    (net (code "40") (name "Net-(J1-SHLD-PadSHLD1)") (class "Default")
      (node (ref "J1") (pin "SHLD1") (pinfunction "SHLD_SHLD1") (pintype "bidirectional"))
      (node (ref "J1") (pin "SHLD2") (pinfunction "SHLD_SHLD2") (pintype "bidirectional"))
      (node (ref "J1") (pin "SHLD3") (pinfunction "SHLD_SHLD3") (pintype "bidirectional"))
      (node (ref "J1") (pin "SHLD4") (pinfunction "SHLD_SHLD4") (pintype "bidirectional"))
      (node (ref "SH") (pin "1") (pinfunction "1_1") (pintype "passive"))
    )
    (net (code "41") (name "Net-(J4-A3)") (class "Default")
      (node (ref "J4") (pin "21") (pinfunction "A3_21") (pintype "bidirectional"))
      (node (ref "JP3") (pin "1") (pinfunction "1_1") (pintype "passive"))
    )
    (net (code "42") (name "Net-(J4-A4)") (class "Default")
      (node (ref "J4") (pin "20") (pinfunction "A4_20") (pintype "bidirectional"))
      (node (ref "JP2") (pin "1") (pinfunction "1_1") (pintype "passive"))
    )
    (net (code "43") (name "Net-(J4-A5)") (class "Default")
      (node (ref "J4") (pin "19") (pinfunction "A5_19") (pintype "bidirectional"))
      (node (ref "JP1") (pin "1") (pinfunction "1_1") (pintype "passive"))
    )
    (net (code "44") (name "Net-(J4-RX)") (class "Default")
      (node (ref "J4") (pin "15") (pinfunction "RX_15") (pintype "bidirectional"))
      (node (ref "TXD") (pin "1") (pinfunction "1_1") (pintype "passive"))
    )
    (net (code "45") (name "Net-(J4-TX)") (class "Default")
      (node (ref "J4") (pin "14") (pinfunction "TX_14") (pintype "bidirectional"))
      (node (ref "RXD") (pin "1") (pinfunction "1_1") (pintype "passive"))
    )
    (net (code "46") (name "Net-(Q1-G)") (class "Default")
      (node (ref "Q1") (pin "1") (pinfunction "G_1") (pintype "bidirectional"))
      (node (ref "R28") (pin "2") (pinfunction "2_2") (pintype "passive"))
      (node (ref "R7") (pin "1") (pinfunction "1_1") (pintype "passive"))
    )
    (net (code "47") (name "Net-(Q2-D)") (class "Default")
      (node (ref "Q2") (pin "3") (pinfunction "D_3") (pintype "bidirectional"))
      (node (ref "R28") (pin "1") (pinfunction "1_1") (pintype "passive"))
    )
    (net (code "48") (name "Net-(Q2-G)") (class "Default")
      (node (ref "Q2") (pin "1") (pinfunction "G_1") (pintype "bidirectional"))
      (node (ref "R20") (pin "2") (pinfunction "2_2") (pintype "passive"))
      (node (ref "R27") (pin "1") (pinfunction "1_1") (pintype "passive"))
    )
    (net (code "49") (name "Net-(Q3-G)") (class "Default")
      (node (ref "Q3") (pin "1") (pinfunction "G_1") (pintype "bidirectional"))
      (node (ref "R26") (pin "2") (pinfunction "2_2") (pintype "passive"))
      (node (ref "R9") (pin "1") (pinfunction "1_1") (pintype "passive"))
    )
    (net (code "50") (name "Net-(Q4-G)") (class "Default")
      (node (ref "Q4") (pin "1") (pinfunction "G_1") (pintype "bidirectional"))
      (node (ref "Q5") (pin "3") (pinfunction "C_3") (pintype "passive"))
      (node (ref "R22") (pin "2") (pinfunction "2_2") (pintype "passive"))
    )
    (net (code "51") (name "Net-(Q5A-B)") (class "Default")
      (node (ref "Q5") (pin "2") (pinfunction "B_2") (pintype "passive"))
      (node (ref "Q5") (pin "5") (pinfunction "B_5") (pintype "passive"))
      (node (ref "Q5") (pin "6") (pinfunction "C_6") (pintype "passive"))
      (node (ref "R21") (pin "2") (pinfunction "2_2") (pintype "passive"))
    )
    (net (code "52") (name "Net-(Q6-G)") (class "Default")
      (node (ref "Q6") (pin "1") (pinfunction "G_1") (pintype "bidirectional"))
      (node (ref "Q7") (pin "3") (pinfunction "C_3") (pintype "passive"))
      (node (ref "R24") (pin "2") (pinfunction "2_2") (pintype "passive"))
    )
    (net (code "53") (name "Net-(Q7A-B)") (class "Default")
      (node (ref "Q7") (pin "2") (pinfunction "B_2") (pintype "passive"))
      (node (ref "Q7") (pin "5") (pinfunction "B_5") (pintype "passive"))
      (node (ref "Q7") (pin "6") (pinfunction "C_6") (pintype "passive"))
      (node (ref "R23") (pin "2") (pinfunction "2_2") (pintype "passive"))
    )
    (net (code "54") (name "PICO") (class "Default")
      (node (ref "J4") (pin "17") (pinfunction "PICO_17") (pintype "bidirectional"))
      (node (ref "U4") (pin "8") (pinfunction "3Y_8") (pintype "bidirectional"))
    )
    (net (code "55") (name "POCI") (class "Default")
      (node (ref "J4") (pin "16") (pinfunction "POCI_16") (pintype "bidirectional"))
      (node (ref "R30") (pin "2") (pinfunction "2_2") (pintype "passive"))
      (node (ref "U4") (pin "1") (pinfunction "1Y_1") (pintype "bidirectional"))
    )
    (net (code "56") (name "RXD0") (class "Default")
      (node (ref "RXD") (pin "2") (pinfunction "2_2") (pintype "passive"))
      (node (ref "U3") (pin "3") (pinfunction "(RXD0/A2)2_3") (pintype "bidirectional"))
    )
    (net (code "57") (name "SCL") (class "Default")
      (node (ref "J3") (pin "3") (pinfunction "3_3") (pintype "passive"))
      (node (ref "J4") (pin "2") (pinfunction "SCL_2") (pintype "bidirectional"))
      (node (ref "R19") (pin "1") (pinfunction "1_1") (pintype "passive"))
      (node (ref "U3") (pin "1") (pinfunction "(SCL/SCK/A4)4_1") (pintype "bidirectional"))
    )
    (net (code "58") (name "SCLK") (class "Default")
      (node (ref "J4") (pin "18") (pinfunction "SCK_18") (pintype "bidirectional"))
      (node (ref "U4") (pin "11") (pinfunction "4Y_11") (pintype "bidirectional"))
    )
    (net (code "59") (name "SDA") (class "Default")
      (node (ref "J3") (pin "4") (pinfunction "4_4") (pintype "passive"))
      (node (ref "J4") (pin "1") (pinfunction "SDA_1") (pintype "bidirectional"))
      (node (ref "R18") (pin "2") (pinfunction "2_2") (pintype "passive"))
      (node (ref "U3") (pin "16") (pinfunction "(SDA/PICO/A6)6_16") (pintype "bidirectional"))
    )
    (net (code "60") (name "SDIO_EN") (class "Default")
      (node (ref "R27") (pin "2") (pinfunction "2_2") (pintype "passive"))
      (node (ref "U2") (pin "13") (pinfunction "1E_13") (pintype "bidirectional"))
      (node (ref "U2") (pin "5") (pinfunction "2E_5") (pintype "bidirectional"))
      (node (ref "U3") (pin "2") (pinfunction "(A3)3_2") (pintype "bidirectional"))
      (node (ref "U5") (pin "12") (pinfunction "4E_12") (pintype "bidirectional"))
      (node (ref "U5") (pin "13") (pinfunction "1E_13") (pintype "bidirectional"))
      (node (ref "U5") (pin "5") (pinfunction "2E_5") (pintype "bidirectional"))
      (node (ref "U5") (pin "6") (pinfunction "3E_6") (pintype "bidirectional"))
    )
    (net (code "61") (name "SDIO_VDD") (class "Default")
      (node (ref "C14") (pin "1") (pinfunction "1_1") (pintype "passive"))
      (node (ref "C15") (pin "1") (pinfunction "1_1") (pintype "passive"))
      (node (ref "C19") (pin "1") (pinfunction "1_1") (pintype "passive"))
      (node (ref "IC1") (pin "14") (pinfunction "VDD_14") (pintype "power_in"))
      (node (ref "IC1") (pin "22") (pinfunction "VDD_22") (pintype "power_in"))
      (node (ref "IC1") (pin "36") (pinfunction "VDD_36") (pintype "power_in"))
      (node (ref "IC1") (pin "6") (pinfunction "VDD_6") (pintype "power_in"))
      (node (ref "Q1") (pin "3") (pinfunction "D_3") (pintype "bidirectional"))
      (node (ref "R1") (pin "1") (pinfunction "1_1") (pintype "passive"))
      (node (ref "R13") (pin "1") (pinfunction "1_1") (pintype "passive"))
      (node (ref "R14") (pin "1") (pinfunction "1_1") (pintype "passive"))
      (node (ref "SDIO_VDD") (pin "1") (pinfunction "1_1") (pintype "bidirectional"))
      (node (ref "U6") (pin "8") (pinfunction "VCC_8") (pintype "power_in"))
    )
    (net (code "62") (name "SD_CLK") (class "Default")
      (node (ref "IC1") (pin "9") (pinfunction "SD_CLK_9") (pintype "bidirectional"))
      (node (ref "U5") (pin "8") (pinfunction "3Y_8") (pintype "bidirectional"))
    )
    (net (code "63") (name "SD_CMD") (class "Default")
      (node (ref "IC1") (pin "11") (pinfunction "SD_CMD_11") (pintype "bidirectional"))
      (node (ref "U5") (pin "4") (pinfunction "2Y_4") (pintype "bidirectional"))
    )
    (net (code "64") (name "SD_D0") (class "Default")
      (node (ref "IC1") (pin "5") (pinfunction "SD_D0_5") (pintype "bidirectional"))
      (node (ref "U5") (pin "11") (pinfunction "4Y_11") (pintype "bidirectional"))
    )
    (net (code "65") (name "SD_D1") (class "Default")
      (node (ref "IC1") (pin "4") (pinfunction "SD_D1_4") (pintype "bidirectional"))
      (node (ref "U5") (pin "1") (pinfunction "1Y_1") (pintype "bidirectional"))
    )
    (net (code "66") (name "SD_D2") (class "Default")
      (node (ref "IC1") (pin "25") (pinfunction "SD_D2_25") (pintype "bidirectional"))
      (node (ref "U2") (pin "4") (pinfunction "2Y_4") (pintype "bidirectional"))
    )
    (net (code "67") (name "SD_D3") (class "Default")
      (node (ref "IC1") (pin "23") (pinfunction "SD_D3_23") (pintype "bidirectional"))
      (node (ref "U2") (pin "1") (pinfunction "1Y_1") (pintype "bidirectional"))
    )
    (net (code "68") (name "SPI_EN") (class "Default")
      (node (ref "R15") (pin "2") (pinfunction "2_2") (pintype "passive"))
      (node (ref "U3") (pin "11") (pinfunction "(XTAL1/A11)10_11") (pintype "bidirectional"))
      (node (ref "U4") (pin "12") (pinfunction "4E_12") (pintype "bidirectional"))
      (node (ref "U4") (pin "13") (pinfunction "1E_13") (pintype "bidirectional"))
      (node (ref "U4") (pin "5") (pinfunction "2E_5") (pintype "bidirectional"))
      (node (ref "U4") (pin "6") (pinfunction "3E_6") (pintype "bidirectional"))
    )
    (net (code "69") (name "TXD0") (class "Default")
      (node (ref "TXD") (pin "2") (pinfunction "2_2") (pintype "passive"))
      (node (ref "U3") (pin "4") (pinfunction "(TXD0/A1)1_4") (pintype "bidirectional"))
    )
    (net (code "70") (name "VCC") (class "Default")
      (node (ref "C11") (pin "1") (pinfunction "1_1") (pintype "passive"))
      (node (ref "C13") (pin "1") (pinfunction "1_1") (pintype "passive"))
      (node (ref "C18") (pin "1") (pinfunction "1_1") (pintype "passive"))
      (node (ref "C20") (pin "1") (pinfunction "1_1") (pintype "passive"))
      (node (ref "C21") (pin "1") (pinfunction "1_1") (pintype "passive"))
      (node (ref "C22") (pin "1") (pinfunction "1_1") (pintype "passive"))
      (node (ref "C23") (pin "1") (pinfunction "1_1") (pintype "passive"))
      (node (ref "C24") (pin "1") (pinfunction "1_1") (pintype "passive"))
      (node (ref "C8") (pin "1") (pinfunction "1_1") (pintype "passive"))
      (node (ref "C9") (pin "1") (pinfunction "1_1") (pintype "passive"))
      (node (ref "I2C") (pin "2") (pinfunction "2_2") (pintype "passive"))
      (node (ref "J3") (pin "2") (pinfunction "2_2") (pintype "passive"))
      (node (ref "Q1") (pin "2") (pinfunction "S_2") (pintype "bidirectional"))
      (node (ref "Q3") (pin "2") (pinfunction "S_2") (pintype "bidirectional"))
      (node (ref "Q4") (pin "2") (pinfunction "S_2") (pintype "bidirectional"))
      (node (ref "Q5") (pin "4") (pinfunction "E_4") (pintype "passive"))
      (node (ref "Q6") (pin "2") (pinfunction "S_2") (pintype "bidirectional"))
      (node (ref "Q7") (pin "4") (pinfunction "E_4") (pintype "passive"))
      (node (ref "R4") (pin "2") (pinfunction "2_2") (pintype "passive"))
      (node (ref "R7") (pin "2") (pinfunction "2_2") (pintype "passive"))
      (node (ref "R8") (pin "2") (pinfunction "2_2") (pintype "passive"))
      (node (ref "R9") (pin "2") (pinfunction "2_2") (pintype "passive"))
      (node (ref "U2") (pin "14") (pinfunction "VCC_14") (pintype "bidirectional"))
      (node (ref "U3") (pin "9") (pinfunction "VCC_9") (pintype "power_in"))
      (node (ref "U4") (pin "14") (pinfunction "VCC_14") (pintype "bidirectional"))
      (node (ref "U5") (pin "14") (pinfunction "VCC_14") (pintype "bidirectional"))
    )
    (net (code "71") (name "VCC_1") (class "Default")
      (node (ref "C1") (pin "1") (pinfunction "1_1") (pintype "passive"))
      (node (ref "C7") (pin "1") (pinfunction "1_1") (pintype "passive"))
      (node (ref "Q4") (pin "3") (pinfunction "D_3") (pintype "bidirectional"))
      (node (ref "Q5") (pin "1") (pinfunction "E_1") (pintype "passive"))
      (node (ref "U1") (pin "5") (pinfunction "OUT_5") (pintype "passive"))
    )
    (net (code "72") (name "V_USB") (class "Default")
      (node (ref "C6") (pin "1") (pinfunction "1_1") (pintype "passive"))
      (node (ref "D3") (pin "5") (pinfunction "5_5") (pintype "power_in"))
      (node (ref "J1") (pin "VBUS1") (pinfunction "VBUS_VBUS1") (pintype "bidirectional"))
      (node (ref "J1") (pin "VBUS2") (pinfunction "VBUS_VBUS2") (pintype "bidirectional"))
      (node (ref "JP4") (pin "VBUS") (pinfunction "1_VBUS") (pintype "passive"))
      (node (ref "R2") (pin "2") (pinfunction "2_2") (pintype "passive"))
      (node (ref "U1") (pin "1") (pinfunction "IN_1") (pintype "input"))
      (node (ref "U1") (pin "3") (pinfunction "EN_3") (pintype "input"))
    )
    (net (code "73") (name "V_USB_DIV_2") (class "Default")
      (node (ref "R2") (pin "1") (pinfunction "1_1") (pintype "passive"))
      (node (ref "R3") (pin "2") (pinfunction "2_2") (pintype "passive"))
      (node (ref "U3") (pin "14") (pinfunction "(A8)8_14") (pintype "bidirectional"))
    )
    (net (code "74") (name "unconnected-(IC1-GPIO12-Pad24)") (class "Default")
      (node (ref "IC1") (pin "24") (pinfunction "GPIO12_24") (pintype "bidirectional"))
    )
    (net (code "75") (name "unconnected-(IC1-GPIO14-Pad19)") (class "Default")
      (node (ref "IC1") (pin "19") (pinfunction "GPIO14_19") (pintype "bidirectional"))
    )
    (net (code "76") (name "unconnected-(IC1-SD_D4-Pad20)") (class "Default")
      (node (ref "IC1") (pin "20") (pinfunction "SD_D4_20") (pintype "bidirectional"))
    )
    (net (code "77") (name "unconnected-(IC1-SD_D5-Pad10)") (class "Default")
      (node (ref "IC1") (pin "10") (pinfunction "SD_D5_10") (pintype "bidirectional"))
    )
    (net (code "78") (name "unconnected-(IC1-SD_D6-Pad8)") (class "Default")
      (node (ref "IC1") (pin "8") (pinfunction "SD_D6_8") (pintype "bidirectional"))
    )
    (net (code "79") (name "unconnected-(IC1-SD_D7-Pad7)") (class "Default")
      (node (ref "IC1") (pin "7") (pinfunction "SD_D7_7") (pintype "bidirectional"))
    )
    (net (code "80") (name "unconnected-(IC1-SM_~{B}{slash}R-Pad17)") (class "Default")
      (node (ref "IC1") (pin "17") (pinfunction "SM_~{B}/R_17") (pintype "bidirectional"))
    )
    (net (code "81") (name "unconnected-(IC1-~{SM_CE}-Pad15)") (class "Default")
      (node (ref "IC1") (pin "15") (pinfunction "~{SM_CE}_15") (pintype "bidirectional"))
    )
    (net (code "82") (name "unconnected-(IC1-~{SM_RE}-Pad16)") (class "Default")
      (node (ref "IC1") (pin "16") (pinfunction "~{SM_RE}_16") (pintype "bidirectional"))
    )
    (net (code "83") (name "unconnected-(IC1-~{SM_WE}-Pad12)") (class "Default")
      (node (ref "IC1") (pin "12") (pinfunction "~{SM_WE}_12") (pintype "bidirectional"))
    )
    (net (code "84") (name "unconnected-(J4-A0-Pad24)") (class "Default")
      (node (ref "J4") (pin "24") (pinfunction "A0_24") (pintype "bidirectional"))
    )
    (net (code "85") (name "unconnected-(J4-A1-Pad23)") (class "Default")
      (node (ref "J4") (pin "23") (pinfunction "A1_23") (pintype "bidirectional"))
    )
    (net (code "86") (name "unconnected-(J4-A2-Pad22)") (class "Default")
      (node (ref "J4") (pin "22") (pinfunction "A2_22") (pintype "bidirectional"))
    )
    (net (code "87") (name "unconnected-(J4-FREE-Pad13)") (class "Default")
      (node (ref "J4") (pin "13") (pinfunction "FREE_13") (pintype "bidirectional"))
    )
    (net (code "88") (name "unconnected-(J4-GPIO0-Pad9)") (class "Default")
      (node (ref "J4") (pin "9") (pinfunction "GPIO0_9") (pintype "bidirectional"))
    )
    (net (code "89") (name "unconnected-(J4-GPIO1-Pad8)") (class "Default")
      (node (ref "J4") (pin "8") (pinfunction "GPIO1_8") (pintype "bidirectional"))
    )
    (net (code "90") (name "unconnected-(J4-GPIO2-Pad7)") (class "Default")
      (node (ref "J4") (pin "7") (pinfunction "GPIO2_7") (pintype "bidirectional"))
    )
    (net (code "91") (name "unconnected-(J4-GPIO3-Pad6)") (class "Default")
      (node (ref "J4") (pin "6") (pinfunction "GPIO3_6") (pintype "bidirectional"))
    )
    (net (code "92") (name "unconnected-(J4-GPIO4-Pad5)") (class "Default")
      (node (ref "J4") (pin "5") (pinfunction "GPIO4_5") (pintype "bidirectional"))
    )
    (net (code "93") (name "unconnected-(J4-GPIO5-Pad4)") (class "Default")
      (node (ref "J4") (pin "4") (pinfunction "GPIO5_4") (pintype "bidirectional"))
    )
    (net (code "94") (name "unconnected-(J4-GPIO6-Pad3)") (class "Default")
      (node (ref "J4") (pin "3") (pinfunction "GPIO6_3") (pintype "bidirectional"))
    )
    (net (code "95") (name "unconnected-(J4-NC-Pad26)") (class "Default")
      (node (ref "J4") (pin "26") (pinfunction "NC_26") (pintype "bidirectional"))
    )
    (net (code "96") (name "unconnected-(J4-VBAT-Pad12)") (class "Default")
      (node (ref "J4") (pin "12") (pinfunction "VBAT_12") (pintype "bidirectional"))
    )
    (net (code "97") (name "unconnected-(J4-VUSB-Pad10)") (class "Default")
      (node (ref "J4") (pin "10") (pinfunction "VUSB_10") (pintype "bidirectional"))
    )
    (net (code "98") (name "unconnected-(J4-~{EN}-Pad11)") (class "Default")
      (node (ref "J4") (pin "11") (pinfunction "~{EN}_11") (pintype "bidirectional"))
    )
    (net (code "99") (name "unconnected-(J4-~{RESET}-Pad28)") (class "Default")
      (node (ref "J4") (pin "28") (pinfunction "~{RESET}_28") (pintype "bidirectional"))
    )
    (net (code "100") (name "unconnected-(U1-NC-Pad4)") (class "Default")
      (node (ref "U1") (pin "4") (pinfunction "NC_4") (pintype "no_connect"))
    )
    (net (code "101") (name "unconnected-(U2-3Y-Pad8)") (class "Default")
      (node (ref "U2") (pin "8") (pinfunction "3Y_8") (pintype "bidirectional"))
    )
    (net (code "102") (name "unconnected-(U2-3Z-Pad9)") (class "Default")
      (node (ref "U2") (pin "9") (pinfunction "3Z_9") (pintype "bidirectional"))
    )
    (net (code "103") (name "unconnected-(U2-4Y-Pad11)") (class "Default")
      (node (ref "U2") (pin "11") (pinfunction "4Y_11") (pintype "bidirectional"))
    )
    (net (code "104") (name "unconnected-(U2-4Z-Pad10)") (class "Default")
      (node (ref "U2") (pin "10") (pinfunction "4Z_10") (pintype "bidirectional"))
    )
  )
)
